# XR_Preamp.net
KiCad netlist of a schematic drawn in EAGLE
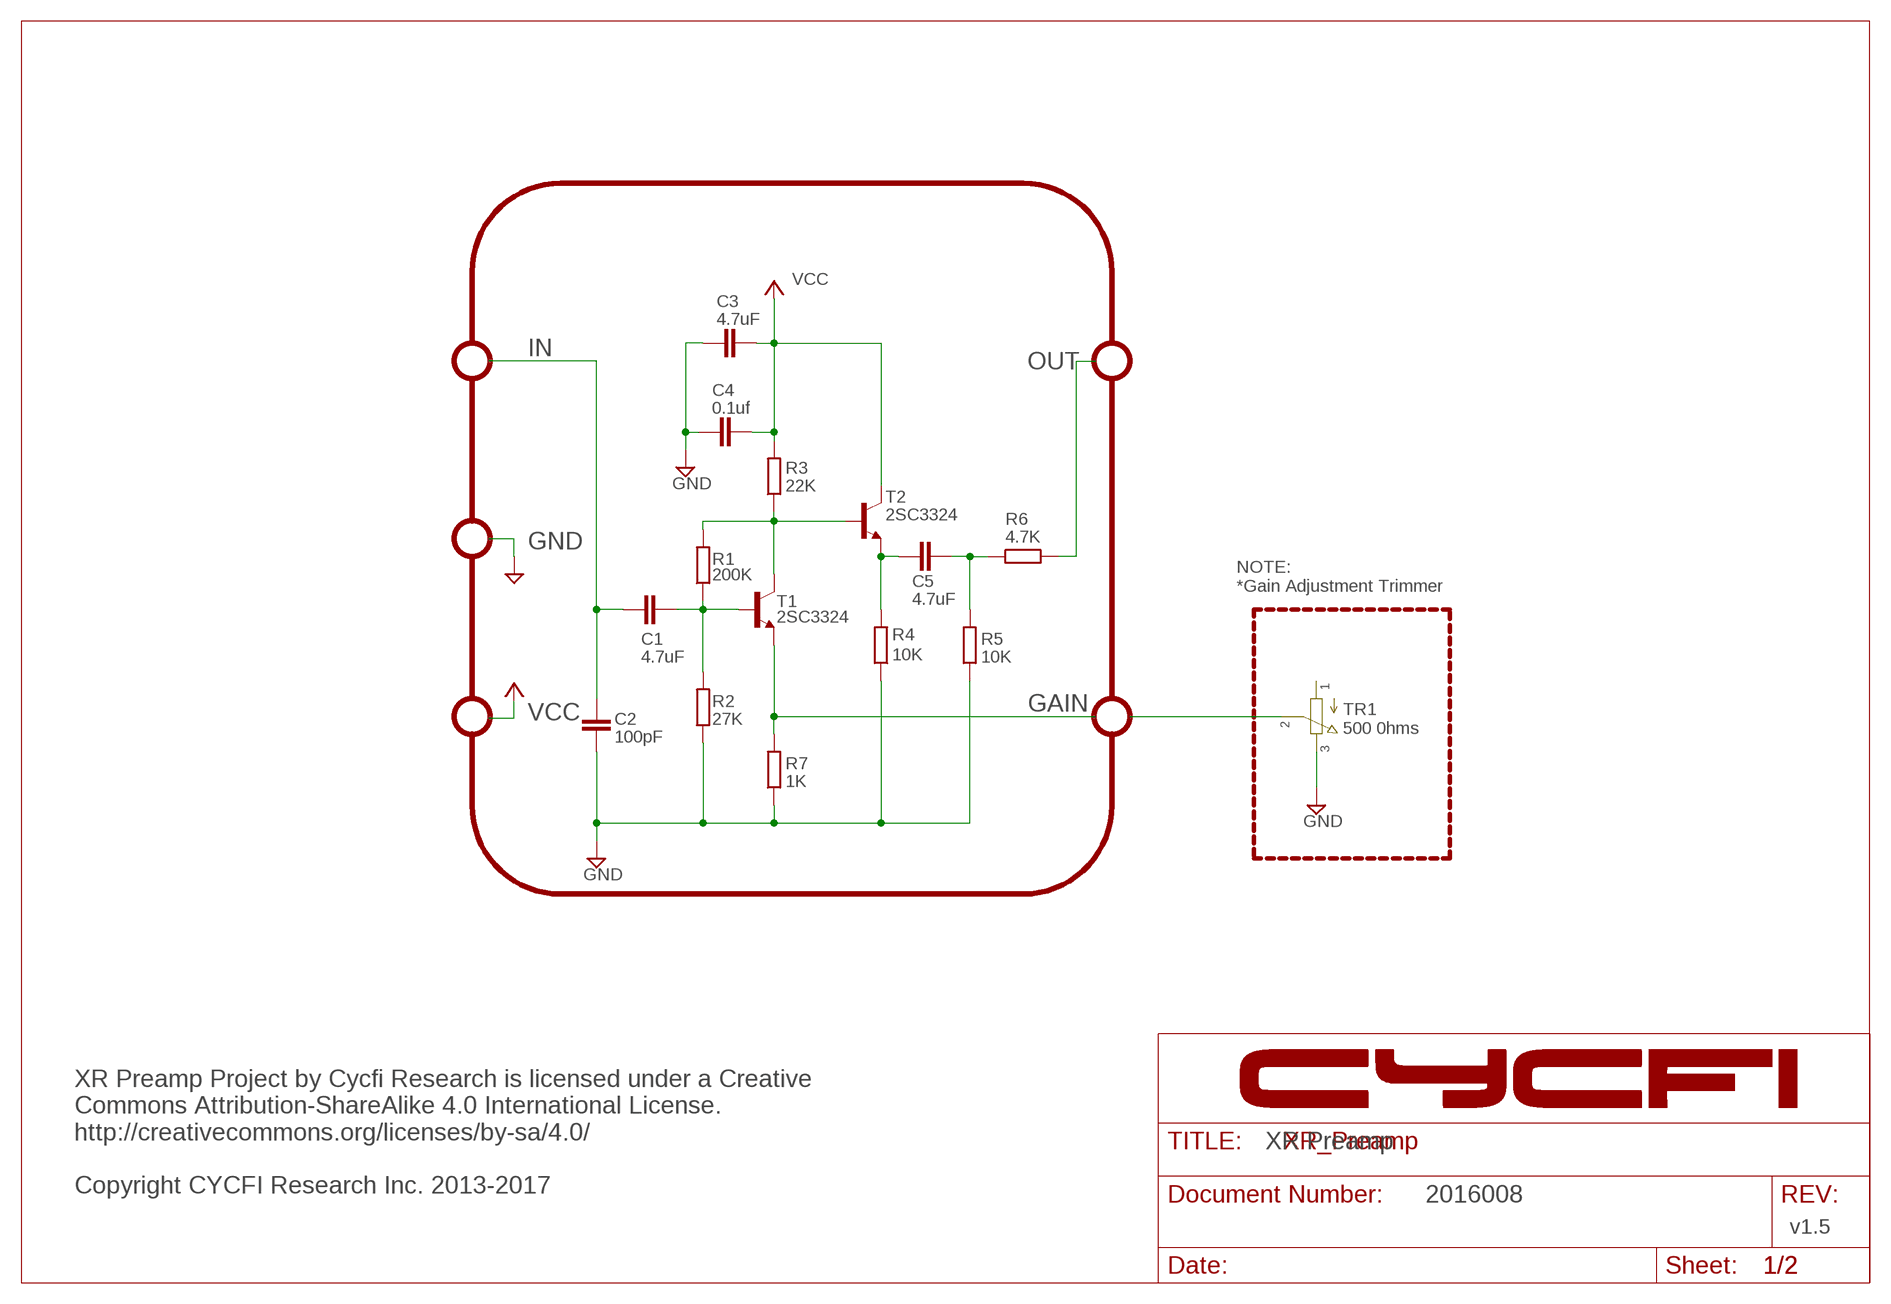
[diagram p0: schematic, sheet 1]
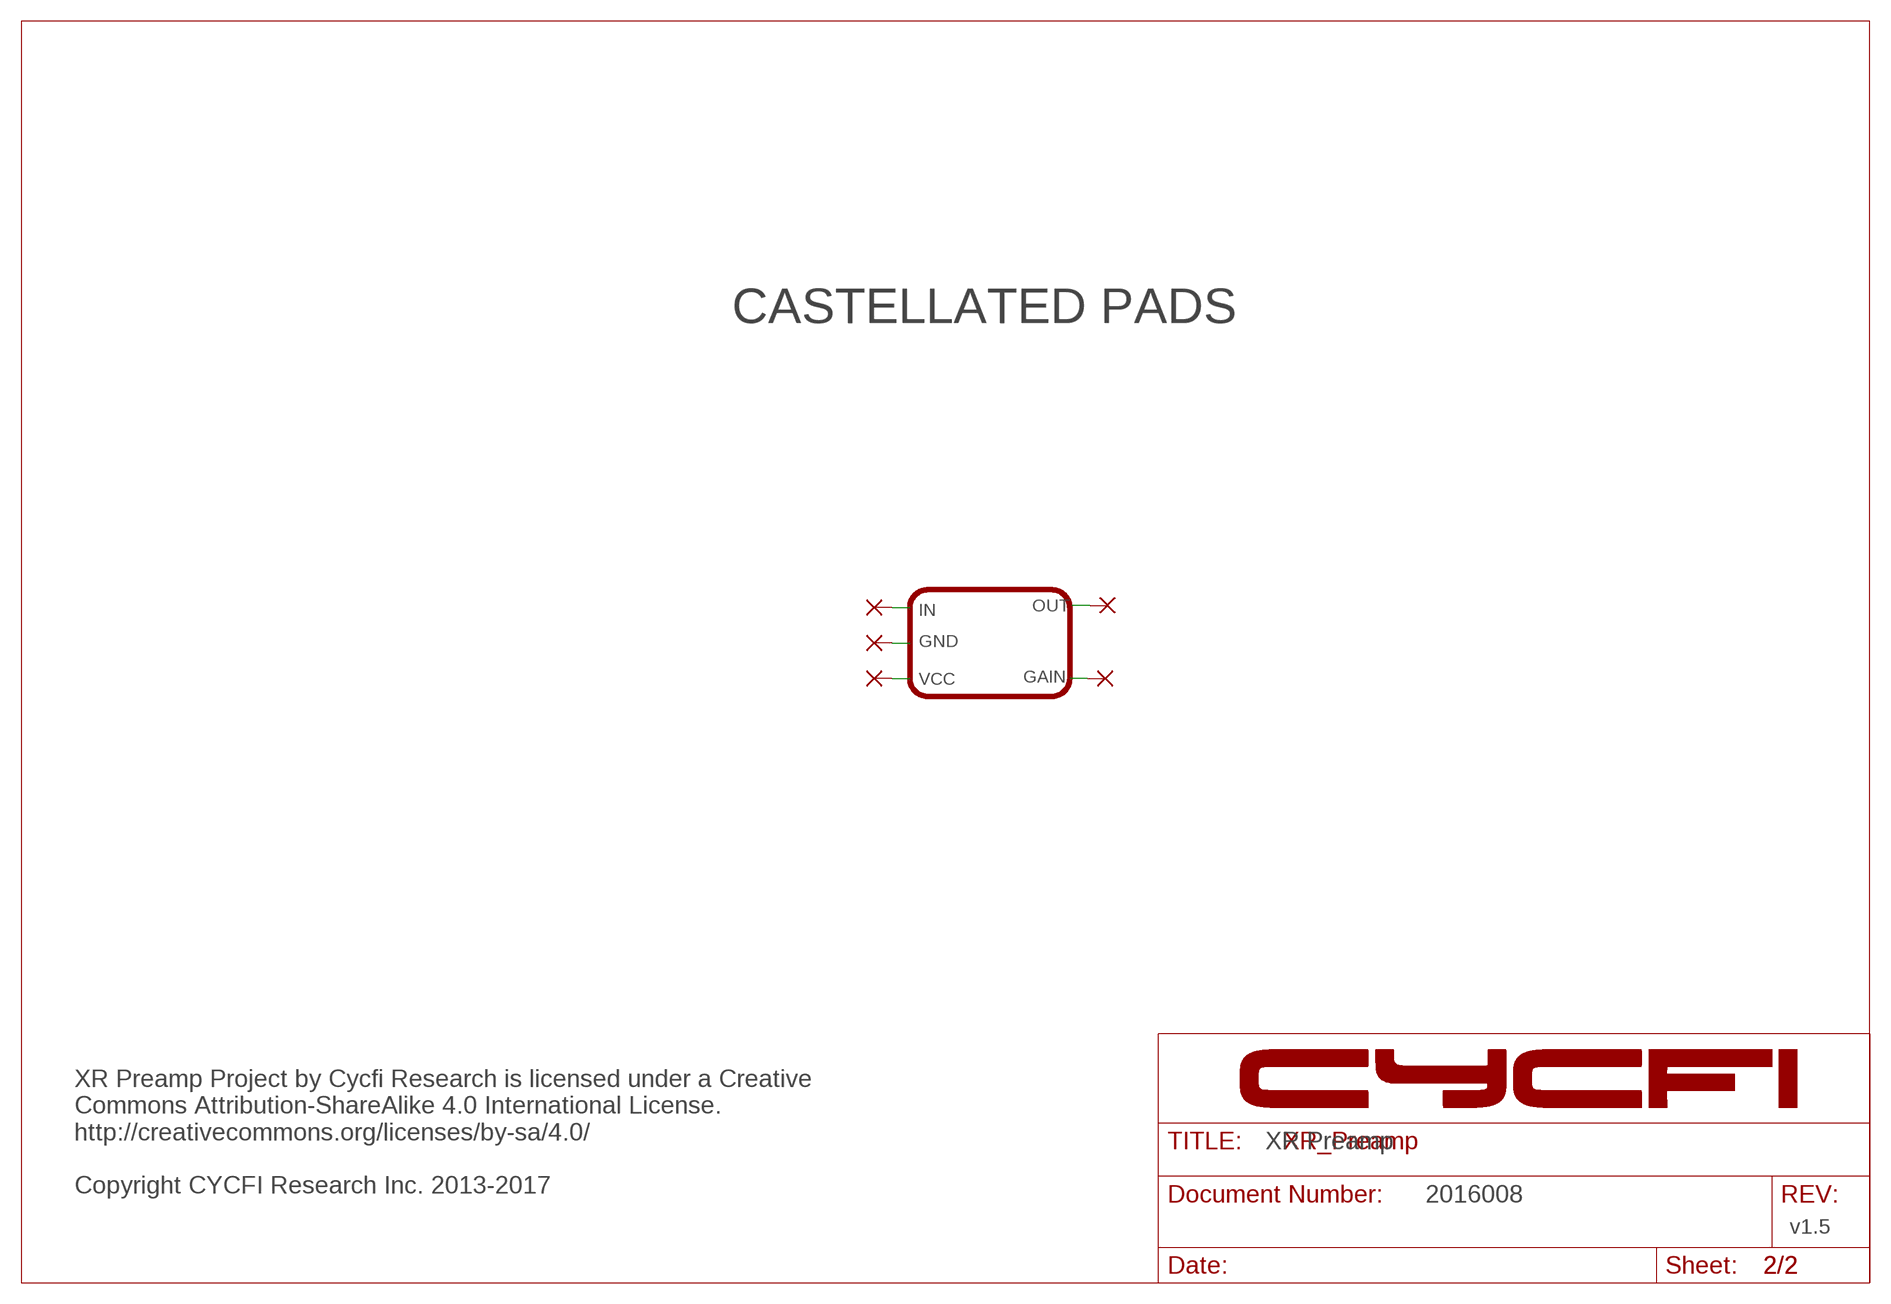
[diagram p1: schematic, sheet 2]

(export (version "E")
  (design (tool "Eeschema 10.0.6"))
  (components
    (comp (ref "C1")
      (value "4.7uF")
      (footprint "eagle-import:C0603")
      (libsource (lib "eagle-import") (part "C-EUC0603"))
    )
    (comp (ref "C2")
      (value "100pF")
      (footprint "eagle-import:C0402")
      (libsource (lib "eagle-import") (part "C-EUC0402"))
    )
    (comp (ref "C3")
      (value "4.7uF")
      (footprint "eagle-import:C0603")
      (libsource (lib "eagle-import") (part "C-EUC0603"))
    )
    (comp (ref "C4")
      (value "0.1uf")
      (footprint "eagle-import:C0402")
      (libsource (lib "eagle-import") (part "C-EUC0402"))
    )
    (comp (ref "C5")
      (value "4.7uF")
      (footprint "eagle-import:C0402")
      (libsource (lib "eagle-import") (part "C-EUC0402"))
    )
    (comp (ref "R1")
      (value "200K")
      (footprint "eagle-import:R0402")
      (libsource (lib "eagle-import") (part "R-EU_R0402"))
    )
    (comp (ref "R2")
      (value "27K")
      (footprint "eagle-import:R0402")
      (libsource (lib "eagle-import") (part "R-EU_R0402"))
    )
    (comp (ref "R3")
      (value "22K")
      (footprint "eagle-import:R0402")
      (libsource (lib "eagle-import") (part "R-EU_R0402"))
    )
    (comp (ref "R4")
      (value "10K")
      (footprint "eagle-import:R0402")
      (libsource (lib "eagle-import") (part "R-EU_R0402"))
    )
    (comp (ref "R5")
      (value "10K")
      (footprint "eagle-import:R0402")
      (libsource (lib "eagle-import") (part "R-EU_R0402"))
    )
    (comp (ref "R6")
      (value "4.7K")
      (footprint "eagle-import:R0402")
      (libsource (lib "eagle-import") (part "R-EU_R0402"))
    )
    (comp (ref "R7")
      (value "1K")
      (footprint "eagle-import:R0402")
      (libsource (lib "eagle-import") (part "R-EU_R0402"))
    )
    (comp (ref "T1")
      (value "2SC3324")
      (footprint "eagle-import:SOT23")
      (libsource (lib "eagle-import") (part "BC846"))
    )
    (comp (ref "T2")
      (value "2SC3324")
      (footprint "eagle-import:SOT23")
      (libsource (lib "eagle-import") (part "BC846"))
    )
    (comp (ref "PAD1")
      (value "WIREPAD2,15/1,0")
      (footprint "eagle-import:1,6_0,8")
      (libsource (lib "eagle-import") (part "1,6/0,8"))
    )
    (comp (ref "PAD2")
      (value "WIREPAD2,15/1,0")
      (footprint "eagle-import:1,6_0,8")
      (libsource (lib "eagle-import") (part "1,6/0,8"))
    )
    (comp (ref "PAD3")
      (value "WIREPAD2,15/1,0")
      (footprint "eagle-import:1,6_0,8")
      (libsource (lib "eagle-import") (part "1,6/0,8"))
    )
    (comp (ref "PAD4")
      (value "WIREPAD2,15/1,0")
      (footprint "eagle-import:1,6_0,8")
      (libsource (lib "eagle-import") (part "1,6/0,8"))
    )
    (comp (ref "PAD5")
      (value "WIREPAD2,15/1,0")
      (footprint "eagle-import:1,6_0,8")
      (libsource (lib "eagle-import") (part "1,6/0,8"))
    )
  )
  (nets
    (net (code "1") (name "GAIN") (class "Default")
      (node (ref "PAD1") (pin "1") (pinfunction "P_1") (pintype "passive"))
      (node (ref "R7") (pin "2") (pinfunction "2_2") (pintype "passive"))
      (node (ref "T1") (pin "2") (pinfunction "E_2") (pintype "passive"))
    )
    (net (code "2") (name "GND") (class "Default")
      (node (ref "C2") (pin "1") (pinfunction "1_1") (pintype "passive"))
      (node (ref "C3") (pin "1") (pinfunction "1_1") (pintype "passive"))
      (node (ref "C4") (pin "1") (pinfunction "1_1") (pintype "passive"))
      (node (ref "PAD2") (pin "1") (pinfunction "P_1") (pintype "passive"))
      (node (ref "R2") (pin "1") (pinfunction "1_1") (pintype "passive"))
      (node (ref "R4") (pin "1") (pinfunction "1_1") (pintype "passive"))
      (node (ref "R5") (pin "1") (pinfunction "1_1") (pintype "passive"))
      (node (ref "R7") (pin "1") (pinfunction "1_1") (pintype "passive"))
    )
    (net (code "3") (name "IN") (class "Default")
      (node (ref "C1") (pin "1") (pinfunction "1_1") (pintype "passive"))
      (node (ref "C2") (pin "2") (pinfunction "2_2") (pintype "passive"))
      (node (ref "PAD3") (pin "1") (pinfunction "P_1") (pintype "passive"))
    )
    (net (code "4") (name "Net-(C5-Pad1)") (class "Default")
      (node (ref "C5") (pin "1") (pinfunction "1_1") (pintype "passive"))
      (node (ref "R5") (pin "2") (pinfunction "2_2") (pintype "passive"))
      (node (ref "R6") (pin "1") (pinfunction "1_1") (pintype "passive"))
    )
    (net (code "5") (name "Net-(T1-B)") (class "Default")
      (node (ref "C1") (pin "2") (pinfunction "2_2") (pintype "passive"))
      (node (ref "R1") (pin "1") (pinfunction "1_1") (pintype "passive"))
      (node (ref "R2") (pin "2") (pinfunction "2_2") (pintype "passive"))
      (node (ref "T1") (pin "1") (pinfunction "B_1") (pintype "passive"))
    )
    (net (code "6") (name "Net-(T1-C)") (class "Default")
      (node (ref "R1") (pin "2") (pinfunction "2_2") (pintype "passive"))
      (node (ref "R3") (pin "1") (pinfunction "1_1") (pintype "passive"))
      (node (ref "T1") (pin "3") (pinfunction "C_3") (pintype "passive"))
      (node (ref "T2") (pin "1") (pinfunction "B_1") (pintype "passive"))
    )
    (net (code "7") (name "Net-(T2-E)") (class "Default")
      (node (ref "C5") (pin "2") (pinfunction "2_2") (pintype "passive"))
      (node (ref "R4") (pin "2") (pinfunction "2_2") (pintype "passive"))
      (node (ref "T2") (pin "2") (pinfunction "E_2") (pintype "passive"))
    )
    (net (code "8") (name "OUT") (class "Default")
      (node (ref "PAD5") (pin "1") (pinfunction "P_1") (pintype "passive"))
      (node (ref "R6") (pin "2") (pinfunction "2_2") (pintype "passive"))
    )
    (net (code "9") (name "VCC") (class "Default")
      (node (ref "C3") (pin "2") (pinfunction "2_2") (pintype "passive"))
      (node (ref "C4") (pin "2") (pinfunction "2_2") (pintype "passive"))
      (node (ref "PAD4") (pin "1") (pinfunction "P_1") (pintype "passive"))
      (node (ref "R3") (pin "2") (pinfunction "2_2") (pintype "passive"))
      (node (ref "T2") (pin "3") (pinfunction "C_3") (pintype "passive"))
    )
  )
)
